# RJ45.net
KiCad netlist of a schematic drawn in Altium Designer
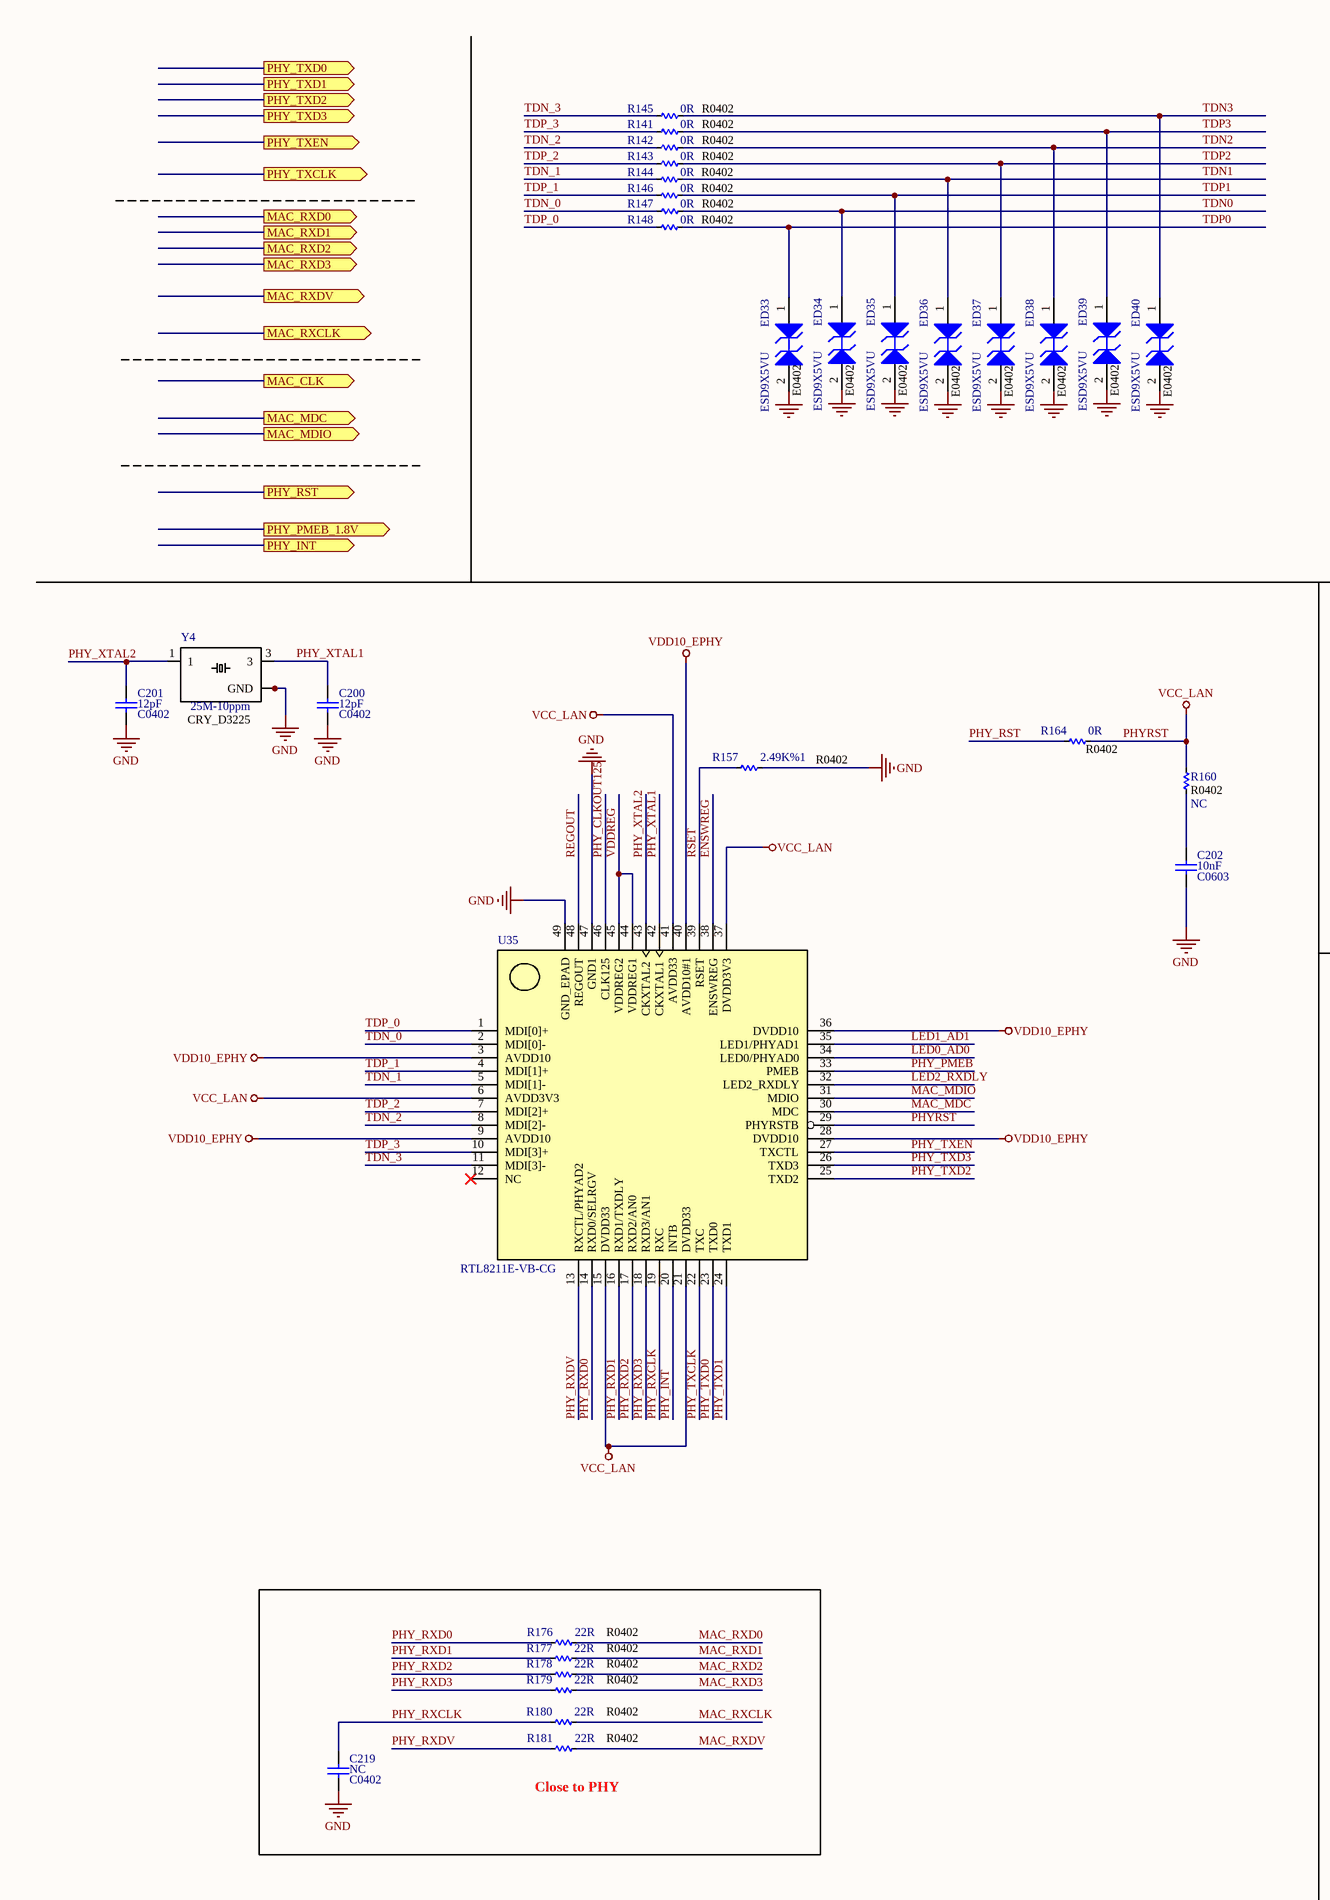
[diagram p0: RJ45.SchDoc, left]
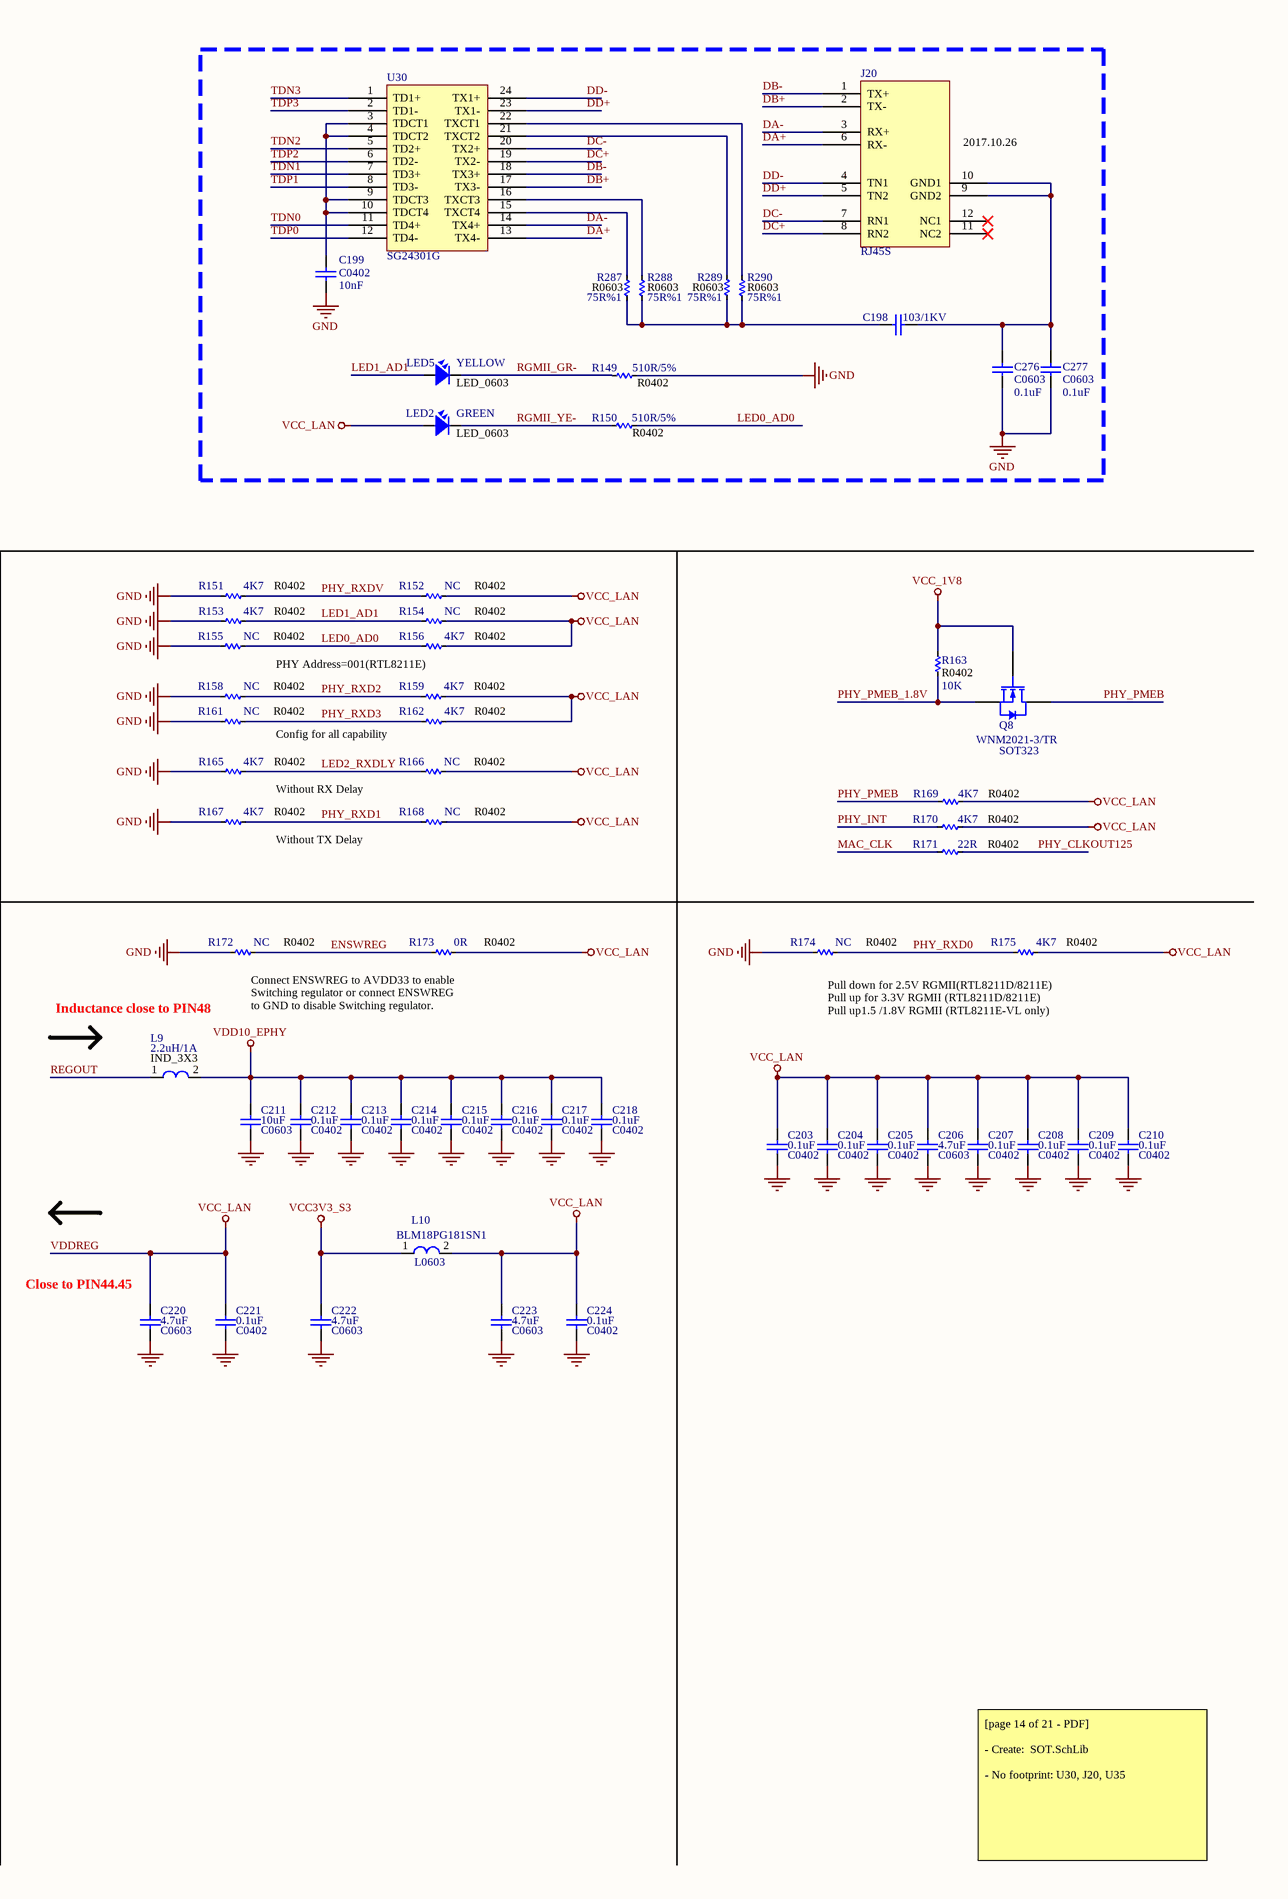
[diagram p1: RJ45.SchDoc, right]

(export (version "E")
  (design (tool "Eeschema 10.0.6"))
  (components
    (comp (ref "C198")
      (value "103/1KV")
      (footprint "C 1206")
      (description "Capacitor")
      (fields (field (name "Comment") "C1206"))
      (libsource (lib "Miscellaneous Devices") (part "Cap"))
    )
    (comp (ref "C199")
      (value "C0402")
      (footprint "C 0402")
      (description "Capacitor")
      (fields (field (name "ALTIUM_VALUE") "10nF"))
      (libsource (lib "Miscellaneous Devices") (part "Cap"))
    )
    (comp (ref "C200")
      (value "C0402")
      (footprint "C 0402")
      (description "Capacitor")
      (fields (field (name "ALTIUM_VALUE") "12pF"))
      (libsource (lib "Miscellaneous Devices") (part "Cap"))
    )
    (comp (ref "C201")
      (value "C0402")
      (footprint "C 0402")
      (description "Capacitor")
      (fields (field (name "ALTIUM_VALUE") "12pF"))
      (libsource (lib "Miscellaneous Devices") (part "Cap"))
    )
    (comp (ref "C202")
      (value "C0603")
      (footprint "C 0603")
      (description "Capacitor")
      (fields (field (name "ALTIUM_VALUE") "10nF"))
      (libsource (lib "Miscellaneous Devices") (part "Cap"))
    )
    (comp (ref "C203")
      (value "C0402")
      (footprint "C 0402")
      (description "Capacitor")
      (fields (field (name "ALTIUM_VALUE") "0.1uF"))
      (libsource (lib "Miscellaneous Devices") (part "Cap"))
    )
    (comp (ref "C204")
      (value "C0402")
      (footprint "C 0402")
      (description "Capacitor")
      (fields (field (name "ALTIUM_VALUE") "0.1uF"))
      (libsource (lib "Miscellaneous Devices") (part "Cap"))
    )
    (comp (ref "C205")
      (value "C0402")
      (footprint "C 0402")
      (description "Capacitor")
      (fields (field (name "ALTIUM_VALUE") "0.1uF"))
      (libsource (lib "Miscellaneous Devices") (part "Cap"))
    )
    (comp (ref "C206")
      (value "C0603")
      (footprint "C 0603")
      (description "Capacitor")
      (fields (field (name "ALTIUM_VALUE") "4.7uF"))
      (libsource (lib "Miscellaneous Devices") (part "Cap"))
    )
    (comp (ref "C207")
      (value "C0402")
      (footprint "C 0402")
      (description "Capacitor")
      (fields (field (name "ALTIUM_VALUE") "0.1uF"))
      (libsource (lib "Miscellaneous Devices") (part "Cap"))
    )
    (comp (ref "C208")
      (value "C0402")
      (footprint "C 0402")
      (description "Capacitor")
      (fields (field (name "ALTIUM_VALUE") "0.1uF"))
      (libsource (lib "Miscellaneous Devices") (part "Cap"))
    )
    (comp (ref "C209")
      (value "C0402")
      (footprint "C 0402")
      (description "Capacitor")
      (fields (field (name "ALTIUM_VALUE") "0.1uF"))
      (libsource (lib "Miscellaneous Devices") (part "Cap"))
    )
    (comp (ref "C210")
      (value "C0402")
      (footprint "C 0402")
      (description "Capacitor")
      (fields (field (name "ALTIUM_VALUE") "0.1uF"))
      (libsource (lib "Miscellaneous Devices") (part "Cap"))
    )
    (comp (ref "C211")
      (value "C0603")
      (footprint "C 0603")
      (description "Capacitor")
      (fields (field (name "ALTIUM_VALUE") "10uF"))
      (libsource (lib "Miscellaneous Devices") (part "Cap"))
    )
    (comp (ref "C212")
      (value "C0402")
      (footprint "C 0402")
      (description "Capacitor")
      (fields (field (name "ALTIUM_VALUE") "0.1uF"))
      (libsource (lib "Miscellaneous Devices") (part "Cap"))
    )
    (comp (ref "C213")
      (value "C0402")
      (footprint "C 0402")
      (description "Capacitor")
      (fields (field (name "ALTIUM_VALUE") "0.1uF"))
      (libsource (lib "Miscellaneous Devices") (part "Cap"))
    )
    (comp (ref "C214")
      (value "C0402")
      (footprint "C 0402")
      (description "Capacitor")
      (fields (field (name "ALTIUM_VALUE") "0.1uF"))
      (libsource (lib "Miscellaneous Devices") (part "Cap"))
    )
    (comp (ref "C215")
      (value "C0402")
      (footprint "C 0402")
      (description "Capacitor")
      (fields (field (name "ALTIUM_VALUE") "0.1uF"))
      (libsource (lib "Miscellaneous Devices") (part "Cap"))
    )
    (comp (ref "C216")
      (value "C0402")
      (footprint "C 0402")
      (description "Capacitor")
      (fields (field (name "ALTIUM_VALUE") "0.1uF"))
      (libsource (lib "Miscellaneous Devices") (part "Cap"))
    )
    (comp (ref "C217")
      (value "C0402")
      (footprint "C 0402")
      (description "Capacitor")
      (fields (field (name "ALTIUM_VALUE") "0.1uF"))
      (libsource (lib "Miscellaneous Devices") (part "Cap"))
    )
    (comp (ref "C218")
      (value "C0402")
      (footprint "C 0402")
      (description "Capacitor")
      (fields (field (name "ALTIUM_VALUE") "0.1uF"))
      (libsource (lib "Miscellaneous Devices") (part "Cap"))
    )
    (comp (ref "C219")
      (value "C0402")
      (footprint "C 0402")
      (description "Capacitor")
      (fields (field (name "ALTIUM_VALUE") "NC"))
      (libsource (lib "Miscellaneous Devices") (part "Cap"))
    )
    (comp (ref "C220")
      (value "C0603")
      (footprint "C 0603")
      (description "Capacitor")
      (fields (field (name "ALTIUM_VALUE") "4.7uF"))
      (libsource (lib "Miscellaneous Devices") (part "Cap"))
    )
    (comp (ref "C221")
      (value "C0402")
      (footprint "C 0402")
      (description "Capacitor")
      (fields (field (name "ALTIUM_VALUE") "0.1uF"))
      (libsource (lib "Miscellaneous Devices") (part "Cap"))
    )
    (comp (ref "C222")
      (value "C0603")
      (footprint "C 0603")
      (description "Capacitor")
      (fields (field (name "ALTIUM_VALUE") "4.7uF"))
      (libsource (lib "Miscellaneous Devices") (part "Cap"))
    )
    (comp (ref "C223")
      (value "C0603")
      (footprint "C 0603")
      (description "Capacitor")
      (fields (field (name "ALTIUM_VALUE") "4.7uF"))
      (libsource (lib "Miscellaneous Devices") (part "Cap"))
    )
    (comp (ref "C224")
      (value "C0402")
      (footprint "C 0402")
      (description "Capacitor")
      (fields (field (name "ALTIUM_VALUE") "0.1uF"))
      (libsource (lib "Miscellaneous Devices") (part "Cap"))
    )
    (comp (ref "C276")
      (value "C0603")
      (footprint "C 0603")
      (description "Capacitor")
      (fields (field (name "ALTIUM_VALUE") "0.1uF"))
      (libsource (lib "Miscellaneous Devices") (part "Cap"))
    )
    (comp (ref "C277")
      (value "C0603")
      (footprint "C 0603")
      (description "Capacitor")
      (fields (field (name "ALTIUM_VALUE") "0.1uF"))
      (libsource (lib "Miscellaneous Devices") (part "Cap"))
    )
    (comp (ref "ED33")
      (value "ESD9X5VU")
      (footprint "DFN1006-2L")
      (description "600 W Peak Power Zener Transient Voltage Suppressor, Bidirectional, 2-Pin SMB, Tape and Reel")
      (fields
        (field (name "MANUFACTURER") "On Semiconductor")
        (field (name "PARTNUMBER") "1SMB54CAT3")
        (field (name "SIZE") "E0402")
      )
      (libsource (lib "ON Semi Transient Voltage Suppressors (TVS)") (part "1SMB54CAT3"))
    )
    (comp (ref "ED34")
      (value "ESD9X5VU")
      (footprint "DFN1006-2L")
      (description "600 W Peak Power Zener Transient Voltage Suppressor, Bidirectional, 2-Pin SMB, Tape and Reel")
      (fields
        (field (name "MANUFACTURER") "On Semiconductor")
        (field (name "PARTNUMBER") "1SMB54CAT3")
        (field (name "SIZE") "E0402")
      )
      (libsource (lib "ON Semi Transient Voltage Suppressors (TVS)") (part "1SMB54CAT3"))
    )
    (comp (ref "ED35")
      (value "ESD9X5VU")
      (footprint "DFN1006-2L")
      (description "600 W Peak Power Zener Transient Voltage Suppressor, Bidirectional, 2-Pin SMB, Tape and Reel")
      (fields
        (field (name "MANUFACTURER") "On Semiconductor")
        (field (name "PARTNUMBER") "1SMB54CAT3")
        (field (name "SIZE") "E0402")
      )
      (libsource (lib "ON Semi Transient Voltage Suppressors (TVS)") (part "1SMB54CAT3"))
    )
    (comp (ref "ED36")
      (value "ESD9X5VU")
      (footprint "DFN1006-2L")
      (description "600 W Peak Power Zener Transient Voltage Suppressor, Bidirectional, 2-Pin SMB, Tape and Reel")
      (fields
        (field (name "MANUFACTURER") "On Semiconductor")
        (field (name "PARTNUMBER") "1SMB54CAT3")
        (field (name "SIZE") "E0402")
      )
      (libsource (lib "ON Semi Transient Voltage Suppressors (TVS)") (part "1SMB54CAT3"))
    )
    (comp (ref "ED37")
      (value "ESD9X5VU")
      (footprint "DFN1006-2L")
      (description "600 W Peak Power Zener Transient Voltage Suppressor, Bidirectional, 2-Pin SMB, Tape and Reel")
      (fields
        (field (name "MANUFACTURER") "On Semiconductor")
        (field (name "PARTNUMBER") "1SMB54CAT3")
        (field (name "SIZE") "E0402")
      )
      (libsource (lib "ON Semi Transient Voltage Suppressors (TVS)") (part "1SMB54CAT3"))
    )
    (comp (ref "ED38")
      (value "ESD9X5VU")
      (footprint "DFN1006-2L")
      (description "600 W Peak Power Zener Transient Voltage Suppressor, Bidirectional, 2-Pin SMB, Tape and Reel")
      (fields
        (field (name "MANUFACTURER") "On Semiconductor")
        (field (name "PARTNUMBER") "1SMB54CAT3")
        (field (name "SIZE") "E0402")
      )
      (libsource (lib "ON Semi Transient Voltage Suppressors (TVS)") (part "1SMB54CAT3"))
    )
    (comp (ref "ED39")
      (value "ESD9X5VU")
      (footprint "DFN1006-2L")
      (description "600 W Peak Power Zener Transient Voltage Suppressor, Bidirectional, 2-Pin SMB, Tape and Reel")
      (fields
        (field (name "MANUFACTURER") "On Semiconductor")
        (field (name "PARTNUMBER") "1SMB54CAT3")
        (field (name "SIZE") "E0402")
      )
      (libsource (lib "ON Semi Transient Voltage Suppressors (TVS)") (part "1SMB54CAT3"))
    )
    (comp (ref "ED40")
      (value "ESD9X5VU")
      (footprint "DFN1006-2L")
      (description "600 W Peak Power Zener Transient Voltage Suppressor, Bidirectional, 2-Pin SMB, Tape and Reel")
      (fields
        (field (name "MANUFACTURER") "On Semiconductor")
        (field (name "PARTNUMBER") "1SMB54CAT3")
        (field (name "SIZE") "E0402")
      )
      (libsource (lib "ON Semi Transient Voltage Suppressors (TVS)") (part "1SMB54CAT3"))
    )
    (comp (ref "J20") (value "RJ45S") (footprint "RJ45") (libsource (lib "SOT") (part "RJ45S")))
    (comp (ref "L9")
      (value "2.2uH/1A")
      (footprint "L-SMD-M-7.3x4.5")
      (fields
        (field (name "PARTNO") "78477010")
        (field (name "MANUFACTURER") "Wurth Elektronik")
        (field (name "ALTIUM_UNNAMED_1") "IND_3X3")
      )
      (libsource (lib "LIBRARY") (part "L-SMD-1"))
    )
    (comp (ref "L10")
      (value "L0603")
      (footprint "L-SMD-M-12x10")
      (fields
        (field (name "PARTNO") "78477010")
        (field (name "MANUFACTURER") "Wurth Elektronik")
        (field (name "ALTIUM_UNNAMED_1") "BLM18PG181SN1")
      )
      (libsource (lib "LIBRARY") (part "L-SMD-1"))
    )
    (comp (ref "LED2")
      (value "LED SMD")
      (footprint "SM-LED-0805-Green")
      (fields (field (name "PACKAGE") "LED_0603") (field (name "COLOR") "GREEN"))
      (libsource (lib "syhaunguyen") (part "LED-SMD-0805"))
    )
    (comp (ref "LED5")
      (value "LED SMD")
      (footprint "SM-LED-0805-Yellow")
      (fields (field (name "PACKAGE") "LED_0603") (field (name "COLOR") "YELLOW"))
      (libsource (lib "syhaunguyen") (part "LED-SMD-0805"))
    )
    (comp (ref "Q8")
      (value "WNM2021-3/TR")
      (footprint "SOT23")
      (description "20V N-Channel Enhancement Mode MOSFET")
      (fields (field (name "PACKAGEREFERENCE") "SOT323"))
      (libsource (lib "Zetex Discrete MOSFET") (part "ZXM61N02F"))
    )
    (comp (ref "R141")
      (value "R0402")
      (footprint "R 0402")
      (description "Resistor")
      (fields (field (name "MANUFACTURER") "Generic Components") (field (name "ALTIUM_VALUE") "0R"))
      (libsource (lib "LIBRARY") (part "Res-SMD"))
    )
    (comp (ref "R142")
      (value "R0402")
      (footprint "R 0402")
      (description "Resistor")
      (fields (field (name "MANUFACTURER") "Generic Components") (field (name "ALTIUM_VALUE") "0R"))
      (libsource (lib "LIBRARY") (part "Res-SMD"))
    )
    (comp (ref "R143")
      (value "R0402")
      (footprint "R 0402")
      (description "Resistor")
      (fields (field (name "MANUFACTURER") "Generic Components") (field (name "ALTIUM_VALUE") "0R"))
      (libsource (lib "LIBRARY") (part "Res-SMD"))
    )
    (comp (ref "R144")
      (value "R0402")
      (footprint "R 0402")
      (description "Resistor")
      (fields (field (name "MANUFACTURER") "Generic Components") (field (name "ALTIUM_VALUE") "0R"))
      (libsource (lib "LIBRARY") (part "Res-SMD"))
    )
    (comp (ref "R145")
      (value "R0402")
      (footprint "R 0402")
      (description "Resistor")
      (fields (field (name "MANUFACTURER") "Generic Components") (field (name "ALTIUM_VALUE") "0R"))
      (libsource (lib "LIBRARY") (part "Res-SMD"))
    )
    (comp (ref "R146")
      (value "R0402")
      (footprint "R 0402")
      (description "Resistor")
      (fields (field (name "MANUFACTURER") "Generic Components") (field (name "ALTIUM_VALUE") "0R"))
      (libsource (lib "LIBRARY") (part "Res-SMD"))
    )
    (comp (ref "R147")
      (value "R0402")
      (footprint "R 0402")
      (description "Resistor")
      (fields (field (name "MANUFACTURER") "Generic Components") (field (name "ALTIUM_VALUE") "0R"))
      (libsource (lib "LIBRARY") (part "Res-SMD"))
    )
    (comp (ref "R148")
      (value "R0402")
      (footprint "R 0402")
      (description "Resistor")
      (fields (field (name "MANUFACTURER") "Generic Components") (field (name "ALTIUM_VALUE") "0R"))
      (libsource (lib "LIBRARY") (part "Res-SMD"))
    )
    (comp (ref "R149")
      (value "R0402")
      (footprint "R 0402")
      (description "Resistor")
      (fields (field (name "MANUFACTURER") "Generic Components") (field (name "ALTIUM_VALUE") "510R/5%"))
      (libsource (lib "LIBRARY") (part "Res-SMD"))
    )
    (comp (ref "R150")
      (value "R0402")
      (footprint "R 0402")
      (description "Resistor")
      (fields (field (name "MANUFACTURER") "Generic Components") (field (name "ALTIUM_VALUE") "510R/5%"))
      (libsource (lib "LIBRARY") (part "Res-SMD"))
    )
    (comp (ref "R151")
      (value "R0402")
      (footprint "R 0402")
      (description "Resistor")
      (fields (field (name "MANUFACTURER") "Generic Components") (field (name "ALTIUM_VALUE") "4K7"))
      (libsource (lib "LIBRARY") (part "Res-SMD"))
    )
    (comp (ref "R152")
      (value "R0402")
      (footprint "R 0402")
      (description "Resistor")
      (fields (field (name "MANUFACTURER") "Generic Components") (field (name "ALTIUM_VALUE") "NC"))
      (libsource (lib "LIBRARY") (part "Res-SMD"))
    )
    (comp (ref "R153")
      (value "R0402")
      (footprint "R 0402")
      (description "Resistor")
      (fields (field (name "MANUFACTURER") "Generic Components") (field (name "ALTIUM_VALUE") "4K7"))
      (libsource (lib "LIBRARY") (part "Res-SMD"))
    )
    (comp (ref "R154")
      (value "R0402")
      (footprint "R 0402")
      (description "Resistor")
      (fields (field (name "MANUFACTURER") "Generic Components") (field (name "ALTIUM_VALUE") "NC"))
      (libsource (lib "LIBRARY") (part "Res-SMD"))
    )
    (comp (ref "R155")
      (value "R0402")
      (footprint "R 0402")
      (description "Resistor")
      (fields (field (name "MANUFACTURER") "Generic Components") (field (name "ALTIUM_VALUE") "NC"))
      (libsource (lib "LIBRARY") (part "Res-SMD"))
    )
    (comp (ref "R156")
      (value "R0402")
      (footprint "R 0402")
      (description "Resistor")
      (fields (field (name "MANUFACTURER") "Generic Components") (field (name "ALTIUM_VALUE") "4K7"))
      (libsource (lib "LIBRARY") (part "Res-SMD"))
    )
    (comp (ref "R157")
      (value "R0402")
      (footprint "R 0402")
      (description "Resistor")
      (fields (field (name "MANUFACTURER") "Generic Components") (field (name "ALTIUM_VALUE") "2.49K%1"))
      (libsource (lib "LIBRARY") (part "Res-SMD"))
    )
    (comp (ref "R158")
      (value "R0402")
      (footprint "R 0402")
      (description "Resistor")
      (fields (field (name "MANUFACTURER") "Generic Components") (field (name "ALTIUM_VALUE") "NC"))
      (libsource (lib "LIBRARY") (part "Res-SMD"))
    )
    (comp (ref "R159")
      (value "R0402")
      (footprint "R 0402")
      (description "Resistor")
      (fields (field (name "MANUFACTURER") "Generic Components") (field (name "ALTIUM_VALUE") "4K7"))
      (libsource (lib "LIBRARY") (part "Res-SMD"))
    )
    (comp (ref "R160")
      (value "R0402")
      (footprint "R 0402")
      (description "Resistor")
      (fields (field (name "MANUFACTURER") "Generic Components") (field (name "ALTIUM_VALUE") "NC"))
      (libsource (lib "LIBRARY") (part "Res-SMD"))
    )
    (comp (ref "R161")
      (value "R0402")
      (footprint "R 0402")
      (description "Resistor")
      (fields (field (name "MANUFACTURER") "Generic Components") (field (name "ALTIUM_VALUE") "NC"))
      (libsource (lib "LIBRARY") (part "Res-SMD"))
    )
    (comp (ref "R162")
      (value "R0402")
      (footprint "R 0402")
      (description "Resistor")
      (fields (field (name "MANUFACTURER") "Generic Components") (field (name "ALTIUM_VALUE") "4K7"))
      (libsource (lib "LIBRARY") (part "Res-SMD"))
    )
    (comp (ref "R163")
      (value "R0402")
      (footprint "R 0402")
      (description "Resistor")
      (fields (field (name "MANUFACTURER") "Generic Components") (field (name "ALTIUM_VALUE") "10K"))
      (libsource (lib "LIBRARY") (part "Res-SMD"))
    )
    (comp (ref "R164")
      (value "R0402")
      (footprint "R 0402")
      (description "Resistor")
      (fields (field (name "MANUFACTURER") "Generic Components") (field (name "ALTIUM_VALUE") "0R"))
      (libsource (lib "LIBRARY") (part "Res-SMD"))
    )
    (comp (ref "R165")
      (value "R0402")
      (footprint "R 0402")
      (description "Resistor")
      (fields (field (name "MANUFACTURER") "Generic Components") (field (name "ALTIUM_VALUE") "4K7"))
      (libsource (lib "LIBRARY") (part "Res-SMD"))
    )
    (comp (ref "R166")
      (value "R0402")
      (footprint "R 0402")
      (description "Resistor")
      (fields (field (name "MANUFACTURER") "Generic Components") (field (name "ALTIUM_VALUE") "NC"))
      (libsource (lib "LIBRARY") (part "Res-SMD"))
    )
    (comp (ref "R167")
      (value "R0402")
      (footprint "R 0402")
      (description "Resistor")
      (fields (field (name "MANUFACTURER") "Generic Components") (field (name "ALTIUM_VALUE") "4K7"))
      (libsource (lib "LIBRARY") (part "Res-SMD"))
    )
    (comp (ref "R168")
      (value "R0402")
      (footprint "R 0402")
      (description "Resistor")
      (fields (field (name "MANUFACTURER") "Generic Components") (field (name "ALTIUM_VALUE") "NC"))
      (libsource (lib "LIBRARY") (part "Res-SMD"))
    )
    (comp (ref "R169")
      (value "R0402")
      (footprint "R 0402")
      (description "Resistor")
      (fields (field (name "MANUFACTURER") "Generic Components") (field (name "ALTIUM_VALUE") "4K7"))
      (libsource (lib "LIBRARY") (part "Res-SMD"))
    )
    (comp (ref "R170")
      (value "R0402")
      (footprint "R 0402")
      (description "Resistor")
      (fields (field (name "MANUFACTURER") "Generic Components") (field (name "ALTIUM_VALUE") "4K7"))
      (libsource (lib "LIBRARY") (part "Res-SMD"))
    )
    (comp (ref "R171")
      (value "R0402")
      (footprint "R 0402")
      (description "Resistor")
      (fields (field (name "MANUFACTURER") "Generic Components") (field (name "ALTIUM_VALUE") "22R"))
      (libsource (lib "LIBRARY") (part "Res-SMD"))
    )
    (comp (ref "R172")
      (value "R0402")
      (footprint "R 0402")
      (description "Resistor")
      (fields (field (name "MANUFACTURER") "Generic Components") (field (name "ALTIUM_VALUE") "NC"))
      (libsource (lib "LIBRARY") (part "Res-SMD"))
    )
    (comp (ref "R173")
      (value "R0402")
      (footprint "R 0402")
      (description "Resistor")
      (fields (field (name "MANUFACTURER") "Generic Components") (field (name "ALTIUM_VALUE") "0R"))
      (libsource (lib "LIBRARY") (part "Res-SMD"))
    )
    (comp (ref "R174")
      (value "R0402")
      (footprint "R 0402")
      (description "Resistor")
      (fields (field (name "MANUFACTURER") "Generic Components") (field (name "ALTIUM_VALUE") "NC"))
      (libsource (lib "LIBRARY") (part "Res-SMD"))
    )
    (comp (ref "R175")
      (value "R0402")
      (footprint "R 0402")
      (description "Resistor")
      (fields (field (name "MANUFACTURER") "Generic Components") (field (name "ALTIUM_VALUE") "4K7"))
      (libsource (lib "LIBRARY") (part "Res-SMD"))
    )
    (comp (ref "R176")
      (value "R0402")
      (footprint "R 0402")
      (description "Resistor")
      (fields (field (name "MANUFACTURER") "Generic Components") (field (name "ALTIUM_VALUE") "22R"))
      (libsource (lib "LIBRARY") (part "Res-SMD"))
    )
    (comp (ref "R177")
      (value "R0402")
      (footprint "R 0402")
      (description "Resistor")
      (fields (field (name "MANUFACTURER") "Generic Components") (field (name "ALTIUM_VALUE") "22R"))
      (libsource (lib "LIBRARY") (part "Res-SMD"))
    )
    (comp (ref "R178")
      (value "R0402")
      (footprint "R 0402")
      (description "Resistor")
      (fields (field (name "MANUFACTURER") "Generic Components") (field (name "ALTIUM_VALUE") "22R"))
      (libsource (lib "LIBRARY") (part "Res-SMD"))
    )
    (comp (ref "R179")
      (value "R0402")
      (footprint "R 0402")
      (description "Resistor")
      (fields (field (name "MANUFACTURER") "Generic Components") (field (name "ALTIUM_VALUE") "22R"))
      (libsource (lib "LIBRARY") (part "Res-SMD"))
    )
    (comp (ref "R180")
      (value "R0402")
      (footprint "R 0402")
      (description "Resistor")
      (fields (field (name "MANUFACTURER") "Generic Components") (field (name "ALTIUM_VALUE") "22R"))
      (libsource (lib "LIBRARY") (part "Res-SMD"))
    )
    (comp (ref "R181")
      (value "R0402")
      (footprint "R 0402")
      (description "Resistor")
      (fields (field (name "MANUFACTURER") "Generic Components") (field (name "ALTIUM_VALUE") "22R"))
      (libsource (lib "LIBRARY") (part "Res-SMD"))
    )
    (comp (ref "R287")
      (value "R0603")
      (footprint "R 0603")
      (description "Resistor")
      (fields (field (name "MANUFACTURER") "Generic Components") (field (name "ALTIUM_VALUE") "75R%1"))
      (libsource (lib "LIBRARY") (part "Res-SMD"))
    )
    (comp (ref "R288")
      (value "R0603")
      (footprint "R 0603")
      (description "Resistor")
      (fields (field (name "MANUFACTURER") "Generic Components") (field (name "ALTIUM_VALUE") "75R%1"))
      (libsource (lib "LIBRARY") (part "Res-SMD"))
    )
    (comp (ref "R289")
      (value "R0603")
      (footprint "R 0603")
      (description "Resistor")
      (fields (field (name "MANUFACTURER") "Generic Components") (field (name "ALTIUM_VALUE") "75R%1"))
      (libsource (lib "LIBRARY") (part "Res-SMD"))
    )
    (comp (ref "R290")
      (value "R0603")
      (footprint "R 0603")
      (description "Resistor")
      (fields (field (name "MANUFACTURER") "Generic Components") (field (name "ALTIUM_VALUE") "75R%1"))
      (libsource (lib "LIBRARY") (part "Res-SMD"))
    )
    (comp (ref "U30") (value "SG24301G") (footprint "SG24301G") (libsource (lib "SOT") (part "SG24301G")))
    (comp (ref "U35")
      (value "RTL8211E-VB-CG")
      (footprint "QFN48")
      (libsource (lib "SOT") (part "RTL8211E-VB-CG"))
    )
    (comp (ref "Y4")
      (value "25M-10ppm")
      (footprint "Crystal 4-SMD 32x25")
      (description "Ultra Miniature Crystal, SMD Ceramic, 30.000MHZ, 10pF, 10ppm@25C, 10ppm -10+60C,")
      (fields
        (field (name "MF") "Abracon")
        (field (name "MP") "ABM8-30.000MHZ-10-1-U-T")
        (field (name "ALTIUM_UNNAMED_1") "CRY_D3225")
      )
      (libsource (lib "ABM8-30.000MHZ-10-1-U-T") (part "ABM8-30.000MHZ-10-1-U-T"))
    )
  )
  (nets
    (net (code "1") (name "/DA+") (class "Default")
      (node (ref "J20") (pin "6") (pinfunction "RX-_6") (pintype "passive"))
      (node (ref "U30") (pin "13") (pinfunction "TX4-_13") (pintype "passive"))
    )
    (net (code "2") (name "/DA-") (class "Default")
      (node (ref "J20") (pin "3") (pinfunction "RX+_3") (pintype "passive"))
      (node (ref "U30") (pin "14") (pinfunction "TX4+_14") (pintype "passive"))
    )
    (net (code "3") (name "/DB+") (class "Default")
      (node (ref "J20") (pin "2") (pinfunction "TX-_2") (pintype "passive"))
      (node (ref "U30") (pin "17") (pinfunction "TX3-_17") (pintype "passive"))
    )
    (net (code "4") (name "/DB-") (class "Default")
      (node (ref "J20") (pin "1") (pinfunction "TX+_1") (pintype "passive"))
      (node (ref "U30") (pin "18") (pinfunction "TX3+_18") (pintype "passive"))
    )
    (net (code "5") (name "/DC+") (class "Default")
      (node (ref "J20") (pin "8") (pinfunction "RN2_8") (pintype "passive"))
      (node (ref "U30") (pin "19") (pinfunction "TX2-_19") (pintype "passive"))
    )
    (net (code "6") (name "/DC-") (class "Default")
      (node (ref "J20") (pin "7") (pinfunction "RN1_7") (pintype "passive"))
      (node (ref "U30") (pin "20") (pinfunction "TX2+_20") (pintype "passive"))
    )
    (net (code "7") (name "/DD+") (class "Default")
      (node (ref "J20") (pin "5") (pinfunction "TN2_5") (pintype "passive"))
      (node (ref "U30") (pin "23") (pinfunction "TX1-_23") (pintype "passive"))
    )
    (net (code "8") (name "/DD-") (class "Default")
      (node (ref "J20") (pin "4") (pinfunction "TN1_4") (pintype "passive"))
      (node (ref "U30") (pin "24") (pinfunction "TX1+_24") (pintype "passive"))
    )
    (net (code "9") (name "/ENSWREG") (class "Default")
      (node (ref "R172") (pin "2") (pinfunction "2_2") (pintype "passive"))
      (node (ref "R173") (pin "1") (pinfunction "1_1") (pintype "passive"))
      (node (ref "U35") (pin "38") (pinfunction "ENSWREG_38") (pintype "passive"))
    )
    (net (code "10") (name "/LED0_AD0") (class "Default")
      (node (ref "R150") (pin "1") (pinfunction "1_1") (pintype "passive"))
      (node (ref "R155") (pin "2") (pinfunction "2_2") (pintype "passive"))
      (node (ref "R156") (pin "1") (pinfunction "1_1") (pintype "passive"))
      (node (ref "U35") (pin "34") (pinfunction "LED0/PHYAD0_34") (pintype "passive"))
    )
    (net (code "11") (name "/LED1_AD1") (class "Default")
      (node (ref "LED5") (pin "1") (pinfunction "1_1") (pintype "passive"))
      (node (ref "R153") (pin "2") (pinfunction "2_2") (pintype "passive"))
      (node (ref "R154") (pin "1") (pinfunction "1_1") (pintype "passive"))
      (node (ref "U35") (pin "35") (pinfunction "LED1/PHYAD1_35") (pintype "passive"))
    )
    (net (code "12") (name "/LED2_RXDLY") (class "Default")
      (node (ref "R165") (pin "2") (pinfunction "2_2") (pintype "passive"))
      (node (ref "R166") (pin "1") (pinfunction "1_1") (pintype "passive"))
      (node (ref "U35") (pin "32") (pinfunction "LED2_RXDLY_32") (pintype "passive"))
    )
    (net (code "13") (name "/MAC_CLK") (class "Default")
      (node (ref "R171") (pin "1") (pinfunction "1_1") (pintype "passive"))
    )
    (net (code "14") (name "/MAC_MDC") (class "Default")
      (node (ref "U35") (pin "30") (pinfunction "MDC_30") (pintype "passive"))
    )
    (net (code "15") (name "/MAC_MDIO") (class "Default")
      (node (ref "U35") (pin "31") (pinfunction "MDIO_31") (pintype "passive"))
    )
    (net (code "16") (name "/MAC_RXCLK") (class "Default")
      (node (ref "R180") (pin "2") (pinfunction "2_2") (pintype "passive"))
    )
    (net (code "17") (name "/MAC_RXD0") (class "Default")
      (node (ref "R176") (pin "2") (pinfunction "2_2") (pintype "passive"))
    )
    (net (code "18") (name "/MAC_RXD1") (class "Default")
      (node (ref "R177") (pin "2") (pinfunction "2_2") (pintype "passive"))
    )
    (net (code "19") (name "/MAC_RXD2") (class "Default")
      (node (ref "R178") (pin "2") (pinfunction "2_2") (pintype "passive"))
    )
    (net (code "20") (name "/MAC_RXD3") (class "Default")
      (node (ref "R179") (pin "2") (pinfunction "2_2") (pintype "passive"))
    )
    (net (code "21") (name "/MAC_RXDV") (class "Default")
      (node (ref "R181") (pin "2") (pinfunction "2_2") (pintype "passive"))
    )
    (net (code "22") (name "/PHY_CLKOUT125") (class "Default")
      (node (ref "R171") (pin "2") (pinfunction "2_2") (pintype "passive"))
      (node (ref "U35") (pin "46") (pinfunction "CLK125_46") (pintype "passive"))
    )
    (net (code "23") (name "/PHY_INT") (class "Default")
      (node (ref "R170") (pin "1") (pinfunction "1_1") (pintype "passive"))
      (node (ref "U35") (pin "20") (pinfunction "INTB_20") (pintype "passive"))
    )
    (net (code "24") (name "/PHY_PMEB") (class "Default")
      (node (ref "Q8") (pin "1") (pinfunction "D_1") (pintype "passive"))
      (node (ref "R169") (pin "1") (pinfunction "1_1") (pintype "passive"))
      (node (ref "U35") (pin "33") (pinfunction "PMEB_33") (pintype "passive"))
    )
    (net (code "25") (name "/PHY_PMEB_1.8V") (class "Default")
      (node (ref "Q8") (pin "2") (pinfunction "S_2") (pintype "passive"))
      (node (ref "R163") (pin "2") (pinfunction "2_2") (pintype "passive"))
    )
    (net (code "26") (name "/PHY_RST") (class "Default")
      (node (ref "R164") (pin "1") (pinfunction "1_1") (pintype "passive"))
    )
    (net (code "27") (name "/PHY_RXCLK") (class "Default")
      (node (ref "C219") (pin "1") (pinfunction "1_1") (pintype "passive"))
      (node (ref "R180") (pin "1") (pinfunction "1_1") (pintype "passive"))
      (node (ref "U35") (pin "19") (pinfunction "RXC_19") (pintype "passive"))
    )
    (net (code "28") (name "/PHY_RXD0") (class "Default")
      (node (ref "R174") (pin "2") (pinfunction "2_2") (pintype "passive"))
      (node (ref "R175") (pin "1") (pinfunction "1_1") (pintype "passive"))
      (node (ref "R176") (pin "1") (pinfunction "1_1") (pintype "passive"))
      (node (ref "U35") (pin "14") (pinfunction "RXD0/SELRGV_14") (pintype "passive"))
    )
    (net (code "29") (name "/PHY_RXD1") (class "Default")
      (node (ref "R167") (pin "2") (pinfunction "2_2") (pintype "passive"))
      (node (ref "R168") (pin "1") (pinfunction "1_1") (pintype "passive"))
      (node (ref "R177") (pin "1") (pinfunction "1_1") (pintype "passive"))
      (node (ref "U35") (pin "16") (pinfunction "RXD1/TXDLY_16") (pintype "passive"))
    )
    (net (code "30") (name "/PHY_RXD2") (class "Default")
      (node (ref "R158") (pin "2") (pinfunction "2_2") (pintype "passive"))
      (node (ref "R159") (pin "1") (pinfunction "1_1") (pintype "passive"))
      (node (ref "R178") (pin "1") (pinfunction "1_1") (pintype "passive"))
      (node (ref "U35") (pin "17") (pinfunction "RXD2/AN0_17") (pintype "passive"))
    )
    (net (code "31") (name "/PHY_RXD3") (class "Default")
      (node (ref "R161") (pin "2") (pinfunction "2_2") (pintype "passive"))
      (node (ref "R162") (pin "1") (pinfunction "1_1") (pintype "passive"))
      (node (ref "R179") (pin "1") (pinfunction "1_1") (pintype "passive"))
      (node (ref "U35") (pin "18") (pinfunction "RXD3/AN1_18") (pintype "passive"))
    )
    (net (code "32") (name "/PHY_RXDV") (class "Default")
      (node (ref "R151") (pin "2") (pinfunction "2_2") (pintype "passive"))
      (node (ref "R152") (pin "1") (pinfunction "1_1") (pintype "passive"))
      (node (ref "R181") (pin "1") (pinfunction "1_1") (pintype "passive"))
      (node (ref "U35") (pin "13") (pinfunction "RXCTL/PHYAD2_13") (pintype "passive"))
    )
    (net (code "33") (name "/PHY_TXCLK") (class "Default")
      (node (ref "U35") (pin "22") (pinfunction "TXC_22") (pintype "passive"))
    )
    (net (code "34") (name "/PHY_TXD0") (class "Default")
      (node (ref "U35") (pin "23") (pinfunction "TXD0_23") (pintype "passive"))
    )
    (net (code "35") (name "/PHY_TXD1") (class "Default")
      (node (ref "U35") (pin "24") (pinfunction "TXD1_24") (pintype "passive"))
    )
    (net (code "36") (name "/PHY_TXD2") (class "Default")
      (node (ref "U35") (pin "25") (pinfunction "TXD2_25") (pintype "passive"))
    )
    (net (code "37") (name "/PHY_TXD3") (class "Default")
      (node (ref "U35") (pin "26") (pinfunction "TXD3_26") (pintype "passive"))
    )
    (net (code "38") (name "/PHY_TXEN") (class "Default")
      (node (ref "U35") (pin "27") (pinfunction "TXCTL_27") (pintype "passive"))
    )
    (net (code "39") (name "/PHY_XTAL1") (class "Default")
      (node (ref "C200") (pin "1") (pinfunction "1_1") (pintype "passive"))
      (node (ref "U35") (pin "42") (pinfunction "CKXTAL1_42") (pintype "passive"))
      (node (ref "Y4") (pin "3") (pinfunction "3_3") (pintype "passive"))
    )
    (net (code "40") (name "/PHY_XTAL2") (class "Default")
      (node (ref "C201") (pin "1") (pinfunction "1_1") (pintype "passive"))
      (node (ref "U35") (pin "43") (pinfunction "CKXTAL2_43") (pintype "passive"))
      (node (ref "Y4") (pin "1") (pinfunction "1_1") (pintype "passive"))
    )
    (net (code "41") (name "/REGOUT") (class "Default")
      (node (ref "L9") (pin "1") (pinfunction "1_1") (pintype "passive"))
      (node (ref "U35") (pin "48") (pinfunction "REGOUT_48") (pintype "passive"))
    )
    (net (code "42") (name "/RGMII_GR-") (class "Default")
      (node (ref "LED5") (pin "2") (pinfunction "2_2") (pintype "passive"))
      (node (ref "R149") (pin "2") (pinfunction "2_2") (pintype "passive"))
    )
    (net (code "43") (name "/RGMII_YE-") (class "Default")
      (node (ref "LED2") (pin "2") (pinfunction "2_2") (pintype "passive"))
      (node (ref "R150") (pin "2") (pinfunction "2_2") (pintype "passive"))
    )
    (net (code "44") (name "/RSET") (class "Default")
      (node (ref "R157") (pin "1") (pinfunction "1_1") (pintype "passive"))
      (node (ref "U35") (pin "39") (pinfunction "RSET_39") (pintype "passive"))
    )
    (net (code "45") (name "/TDN0") (class "Default")
      (node (ref "ED34") (pin "1") (pinfunction "A1_1") (pintype "passive"))
      (node (ref "R147") (pin "2") (pinfunction "2_2") (pintype "passive"))
      (node (ref "U30") (pin "11") (pinfunction "TD4+_11") (pintype "passive"))
    )
    (net (code "46") (name "/TDN1") (class "Default")
      (node (ref "ED36") (pin "1") (pinfunction "A1_1") (pintype "passive"))
      (node (ref "R144") (pin "2") (pinfunction "2_2") (pintype "passive"))
      (node (ref "U30") (pin "7") (pinfunction "TD3+_7") (pintype "passive"))
    )
    (net (code "47") (name "/TDN2") (class "Default")
      (node (ref "ED38") (pin "1") (pinfunction "A1_1") (pintype "passive"))
      (node (ref "R142") (pin "2") (pinfunction "2_2") (pintype "passive"))
      (node (ref "U30") (pin "5") (pinfunction "TD2+_5") (pintype "passive"))
    )
    (net (code "48") (name "/TDN3") (class "Default")
      (node (ref "ED40") (pin "1") (pinfunction "A1_1") (pintype "passive"))
      (node (ref "R145") (pin "2") (pinfunction "2_2") (pintype "passive"))
      (node (ref "U30") (pin "1") (pinfunction "TD1+_1") (pintype "passive"))
    )
    (net (code "49") (name "/TDN_0") (class "Default")
      (node (ref "R147") (pin "1") (pinfunction "1_1") (pintype "passive"))
      (node (ref "U35") (pin "2") (pinfunction "MDI[0]-_2") (pintype "passive"))
    )
    (net (code "50") (name "/TDN_1") (class "Default")
      (node (ref "R144") (pin "1") (pinfunction "1_1") (pintype "passive"))
      (node (ref "U35") (pin "5") (pinfunction "MDI[1]-_5") (pintype "passive"))
    )
    (net (code "51") (name "/TDN_2") (class "Default")
      (node (ref "R142") (pin "1") (pinfunction "1_1") (pintype "passive"))
      (node (ref "U35") (pin "8") (pinfunction "MDI[2]-_8") (pintype "passive"))
    )
    (net (code "52") (name "/TDN_3") (class "Default")
      (node (ref "R145") (pin "1") (pinfunction "1_1") (pintype "passive"))
      (node (ref "U35") (pin "11") (pinfunction "MDI[3]-_11") (pintype "passive"))
    )
    (net (code "53") (name "/TDP0") (class "Default")
      (node (ref "ED33") (pin "1") (pinfunction "A1_1") (pintype "passive"))
      (node (ref "R148") (pin "2") (pinfunction "2_2") (pintype "passive"))
      (node (ref "U30") (pin "12") (pinfunction "TD4-_12") (pintype "passive"))
    )
    (net (code "54") (name "/TDP1") (class "Default")
      (node (ref "ED35") (pin "1") (pinfunction "A1_1") (pintype "passive"))
      (node (ref "R146") (pin "2") (pinfunction "2_2") (pintype "passive"))
      (node (ref "U30") (pin "8") (pinfunction "TD3-_8") (pintype "passive"))
    )
    (net (code "55") (name "/TDP2") (class "Default")
      (node (ref "ED37") (pin "1") (pinfunction "A1_1") (pintype "passive"))
      (node (ref "R143") (pin "2") (pinfunction "2_2") (pintype "passive"))
      (node (ref "U30") (pin "6") (pinfunction "TD2-_6") (pintype "passive"))
    )
    (net (code "56") (name "/TDP3") (class "Default")
      (node (ref "ED39") (pin "1") (pinfunction "A1_1") (pintype "passive"))
      (node (ref "R141") (pin "2") (pinfunction "2_2") (pintype "passive"))
      (node (ref "U30") (pin "2") (pinfunction "TD1-_2") (pintype "passive"))
    )
    (net (code "57") (name "/TDP_0") (class "Default")
      (node (ref "R148") (pin "1") (pinfunction "1_1") (pintype "passive"))
      (node (ref "U35") (pin "1") (pinfunction "MDI[0]+_1") (pintype "passive"))
    )
    (net (code "58") (name "/TDP_1") (class "Default")
      (node (ref "R146") (pin "1") (pinfunction "1_1") (pintype "passive"))
      (node (ref "U35") (pin "4") (pinfunction "MDI[1]+_4") (pintype "passive"))
    )
    (net (code "59") (name "/TDP_2") (class "Default")
      (node (ref "R143") (pin "1") (pinfunction "1_1") (pintype "passive"))
      (node (ref "U35") (pin "7") (pinfunction "MDI[2]+_7") (pintype "passive"))
    )
    (net (code "60") (name "/TDP_3") (class "Default")
      (node (ref "R141") (pin "1") (pinfunction "1_1") (pintype "passive"))
      (node (ref "U35") (pin "10") (pinfunction "MDI[3]+_10") (pintype "passive"))
    )
    (net (code "61") (name "GND") (class "Default")
      (node (ref "C199") (pin "1") (pinfunction "1_1") (pintype "passive"))
      (node (ref "C200") (pin "2") (pinfunction "2_2") (pintype "passive"))
      (node (ref "C201") (pin "2") (pinfunction "2_2") (pintype "passive"))
      (node (ref "C202") (pin "2") (pinfunction "2_2") (pintype "passive"))
      (node (ref "C203") (pin "2") (pinfunction "2_2") (pintype "passive"))
      (node (ref "C204") (pin "2") (pinfunction "2_2") (pintype "passive"))
      (node (ref "C205") (pin "2") (pinfunction "2_2") (pintype "passive"))
      (node (ref "C206") (pin "2") (pinfunction "2_2") (pintype "passive"))
      (node (ref "C207") (pin "2") (pinfunction "2_2") (pintype "passive"))
      (node (ref "C208") (pin "2") (pinfunction "2_2") (pintype "passive"))
      (node (ref "C209") (pin "2") (pinfunction "2_2") (pintype "passive"))
      (node (ref "C210") (pin "2") (pinfunction "2_2") (pintype "passive"))
      (node (ref "C211") (pin "2") (pinfunction "2_2") (pintype "passive"))
      (node (ref "C212") (pin "2") (pinfunction "2_2") (pintype "passive"))
      (node (ref "C213") (pin "2") (pinfunction "2_2") (pintype "passive"))
      (node (ref "C214") (pin "2") (pinfunction "2_2") (pintype "passive"))
      (node (ref "C215") (pin "2") (pinfunction "2_2") (pintype "passive"))
      (node (ref "C216") (pin "2") (pinfunction "2_2") (pintype "passive"))
      (node (ref "C217") (pin "2") (pinfunction "2_2") (pintype "passive"))
      (node (ref "C218") (pin "2") (pinfunction "2_2") (pintype "passive"))
      (node (ref "C219") (pin "2") (pinfunction "2_2") (pintype "passive"))
      (node (ref "C220") (pin "2") (pinfunction "2_2") (pintype "passive"))
      (node (ref "C221") (pin "2") (pinfunction "2_2") (pintype "passive"))
      (node (ref "C222") (pin "2") (pinfunction "2_2") (pintype "passive"))
      (node (ref "C223") (pin "2") (pinfunction "2_2") (pintype "passive"))
      (node (ref "C224") (pin "2") (pinfunction "2_2") (pintype "passive"))
      (node (ref "C276") (pin "2") (pinfunction "2_2") (pintype "passive"))
      (node (ref "C277") (pin "2") (pinfunction "2_2") (pintype "passive"))
      (node (ref "ED33") (pin "2") (pinfunction "A2_2") (pintype "passive"))
      (node (ref "ED34") (pin "2") (pinfunction "A2_2") (pintype "passive"))
      (node (ref "ED35") (pin "2") (pinfunction "A2_2") (pintype "passive"))
      (node (ref "ED36") (pin "2") (pinfunction "A2_2") (pintype "passive"))
      (node (ref "ED37") (pin "2") (pinfunction "A2_2") (pintype "passive"))
      (node (ref "ED38") (pin "2") (pinfunction "A2_2") (pintype "passive"))
      (node (ref "ED39") (pin "2") (pinfunction "A2_2") (pintype "passive"))
      (node (ref "ED40") (pin "2") (pinfunction "A2_2") (pintype "passive"))
      (node (ref "R149") (pin "1") (pinfunction "1_1") (pintype "passive"))
      (node (ref "R151") (pin "1") (pinfunction "1_1") (pintype "passive"))
      (node (ref "R153") (pin "1") (pinfunction "1_1") (pintype "passive"))
      (node (ref "R155") (pin "1") (pinfunction "1_1") (pintype "passive"))
      (node (ref "R157") (pin "2") (pinfunction "2_2") (pintype "passive"))
      (node (ref "R158") (pin "1") (pinfunction "1_1") (pintype "passive"))
      (node (ref "R161") (pin "1") (pinfunction "1_1") (pintype "passive"))
      (node (ref "R165") (pin "1") (pinfunction "1_1") (pintype "passive"))
      (node (ref "R167") (pin "1") (pinfunction "1_1") (pintype "passive"))
      (node (ref "R172") (pin "1") (pinfunction "1_1") (pintype "passive"))
      (node (ref "R174") (pin "1") (pinfunction "1_1") (pintype "passive"))
      (node (ref "U35") (pin "47") (pinfunction "GND1_47") (pintype "passive"))
      (node (ref "U35") (pin "49") (pinfunction "GND_EPAD_49") (pintype "passive"))
      (node (ref "Y4") (pin "2") (pinfunction "GND_2") (pintype "power_in"))
      (node (ref "Y4") (pin "4") (pinfunction "GND_4") (pintype "power_in"))
    )
    (net (code "62") (name "Net-(C198-Pad2)") (class "Default")
      (node (ref "C198") (pin "2") (pinfunction "2_2") (pintype "passive"))
      (node (ref "R287") (pin "1") (pinfunction "1_1") (pintype "passive"))
      (node (ref "R288") (pin "1") (pinfunction "1_1") (pintype "passive"))
      (node (ref "R289") (pin "1") (pinfunction "1_1") (pintype "passive"))
      (node (ref "R290") (pin "1") (pinfunction "1_1") (pintype "passive"))
    )
    (net (code "63") (name "Net-(C202-Pad1)") (class "Default")
      (node (ref "C202") (pin "1") (pinfunction "1_1") (pintype "passive"))
      (node (ref "R160") (pin "1") (pinfunction "1_1") (pintype "passive"))
    )
    (net (code "64") (name "Net-(J20-GND1)") (class "Default")
      (node (ref "C198") (pin "1") (pinfunction "1_1") (pintype "passive"))
      (node (ref "C276") (pin "1") (pinfunction "1_1") (pintype "passive"))
      (node (ref "C277") (pin "1") (pinfunction "1_1") (pintype "passive"))
      (node (ref "J20") (pin "10") (pinfunction "GND1_10") (pintype "passive"))
      (node (ref "J20") (pin "9") (pinfunction "GND2_9") (pintype "passive"))
    )
    (net (code "65") (name "Net-(U30-TDCT1)") (class "Default")
      (node (ref "C199") (pin "2") (pinfunction "2_2") (pintype "passive"))
      (node (ref "U30") (pin "10") (pinfunction "TDCT4_10") (pintype "passive"))
      (node (ref "U30") (pin "3") (pinfunction "TDCT1_3") (pintype "passive"))
      (node (ref "U30") (pin "4") (pinfunction "TDCT2_4") (pintype "passive"))
      (node (ref "U30") (pin "9") (pinfunction "TDCT3_9") (pintype "passive"))
    )
    (net (code "66") (name "Net-(U30-TXCT1)") (class "Default")
      (node (ref "R290") (pin "2") (pinfunction "2_2") (pintype "passive"))
      (node (ref "U30") (pin "22") (pinfunction "TXCT1_22") (pintype "passive"))
    )
    (net (code "67") (name "Net-(U30-TXCT2)") (class "Default")
      (node (ref "R289") (pin "2") (pinfunction "2_2") (pintype "passive"))
      (node (ref "U30") (pin "21") (pinfunction "TXCT2_21") (pintype "passive"))
    )
    (net (code "68") (name "Net-(U30-TXCT3)") (class "Default")
      (node (ref "R288") (pin "2") (pinfunction "2_2") (pintype "passive"))
      (node (ref "U30") (pin "16") (pinfunction "TXCT3_16") (pintype "passive"))
    )
    (net (code "69") (name "Net-(U30-TXCT4)") (class "Default")
      (node (ref "R287") (pin "2") (pinfunction "2_2") (pintype "passive"))
      (node (ref "U30") (pin "15") (pinfunction "TXCT4_15") (pintype "passive"))
    )
    (net (code "70") (name "VCC3V3_S3") (class "Default")
      (node (ref "C222") (pin "1") (pinfunction "1_1") (pintype "passive"))
      (node (ref "L10") (pin "1") (pinfunction "1_1") (pintype "passive"))
    )
    (net (code "71") (name "VCC_1V8") (class "Default")
      (node (ref "Q8") (pin "3") (pinfunction "G_3") (pintype "passive"))
      (node (ref "R163") (pin "1") (pinfunction "1_1") (pintype "passive"))
    )
    (net (code "72") (name "VCC_LAN") (class "Default")
      (node (ref "C203") (pin "1") (pinfunction "1_1") (pintype "passive"))
      (node (ref "C204") (pin "1") (pinfunction "1_1") (pintype "passive"))
      (node (ref "C205") (pin "1") (pinfunction "1_1") (pintype "passive"))
      (node (ref "C206") (pin "1") (pinfunction "1_1") (pintype "passive"))
      (node (ref "C207") (pin "1") (pinfunction "1_1") (pintype "passive"))
      (node (ref "C208") (pin "1") (pinfunction "1_1") (pintype "passive"))
      (node (ref "C209") (pin "1") (pinfunction "1_1") (pintype "passive"))
      (node (ref "C210") (pin "1") (pinfunction "1_1") (pintype "passive"))
      (node (ref "C220") (pin "1") (pinfunction "1_1") (pintype "passive"))
      (node (ref "C221") (pin "1") (pinfunction "1_1") (pintype "passive"))
      (node (ref "C223") (pin "1") (pinfunction "1_1") (pintype "passive"))
      (node (ref "C224") (pin "1") (pinfunction "1_1") (pintype "passive"))
      (node (ref "L10") (pin "2") (pinfunction "2_2") (pintype "passive"))
      (node (ref "LED2") (pin "1") (pinfunction "1_1") (pintype "passive"))
      (node (ref "R152") (pin "2") (pinfunction "2_2") (pintype "passive"))
      (node (ref "R154") (pin "2") (pinfunction "2_2") (pintype "passive"))
      (node (ref "R156") (pin "2") (pinfunction "2_2") (pintype "passive"))
      (node (ref "R159") (pin "2") (pinfunction "2_2") (pintype "passive"))
      (node (ref "R160") (pin "2") (pinfunction "2_2") (pintype "passive"))
      (node (ref "R162") (pin "2") (pinfunction "2_2") (pintype "passive"))
      (node (ref "R164") (pin "2") (pinfunction "2_2") (pintype "passive"))
      (node (ref "R166") (pin "2") (pinfunction "2_2") (pintype "passive"))
      (node (ref "R168") (pin "2") (pinfunction "2_2") (pintype "passive"))
      (node (ref "R169") (pin "2") (pinfunction "2_2") (pintype "passive"))
      (node (ref "R170") (pin "2") (pinfunction "2_2") (pintype "passive"))
      (node (ref "R173") (pin "2") (pinfunction "2_2") (pintype "passive"))
      (node (ref "R175") (pin "2") (pinfunction "2_2") (pintype "passive"))
      (node (ref "U35") (pin "15") (pinfunction "DVDD33_15") (pintype "passive"))
      (node (ref "U35") (pin "21") (pinfunction "DVDD33_21") (pintype "passive"))
      (node (ref "U35") (pin "29") (pinfunction "PHYRSTB_29") (pintype "passive"))
      (node (ref "U35") (pin "37") (pinfunction "DVDD3V3_37") (pintype "passive"))
      (node (ref "U35") (pin "41") (pinfunction "AVDD33_41") (pintype "passive"))
      (node (ref "U35") (pin "44") (pinfunction "VDDREG1_44") (pintype "passive"))
      (node (ref "U35") (pin "45") (pinfunction "VDDREG2_45") (pintype "passive"))
      (node (ref "U35") (pin "6") (pinfunction "AVDD3V3_6") (pintype "passive"))
    )
    (net (code "73") (name "VDD10_EPHY") (class "Default")
      (node (ref "C211") (pin "1") (pinfunction "1_1") (pintype "passive"))
      (node (ref "C212") (pin "1") (pinfunction "1_1") (pintype "passive"))
      (node (ref "C213") (pin "1") (pinfunction "1_1") (pintype "passive"))
      (node (ref "C214") (pin "1") (pinfunction "1_1") (pintype "passive"))
      (node (ref "C215") (pin "1") (pinfunction "1_1") (pintype "passive"))
      (node (ref "C216") (pin "1") (pinfunction "1_1") (pintype "passive"))
      (node (ref "C217") (pin "1") (pinfunction "1_1") (pintype "passive"))
      (node (ref "C218") (pin "1") (pinfunction "1_1") (pintype "passive"))
      (node (ref "L9") (pin "2") (pinfunction "2_2") (pintype "passive"))
      (node (ref "U35") (pin "28") (pinfunction "DVDD10_28") (pintype "passive"))
      (node (ref "U35") (pin "3") (pinfunction "AVDD10_3") (pintype "passive"))
      (node (ref "U35") (pin "36") (pinfunction "DVDD10_36") (pintype "passive"))
      (node (ref "U35") (pin "40") (pinfunction "AVDD10#1_40") (pintype "passive"))
      (node (ref "U35") (pin "9") (pinfunction "AVDD10_9") (pintype "passive"))
    )
    (net (code "74") (name "unconnected-(J20-NC1-Pad12)") (class "Default")
      (node (ref "J20") (pin "12") (pinfunction "NC1_12") (pintype "passive+no_connect"))
    )
    (net (code "75") (name "unconnected-(J20-NC2-Pad11)") (class "Default")
      (node (ref "J20") (pin "11") (pinfunction "NC2_11") (pintype "passive+no_connect"))
    )
    (net (code "76") (name "unconnected-(U35-NC-Pad12)") (class "Default")
      (node (ref "U35") (pin "12") (pinfunction "NC_12") (pintype "passive+no_connect"))
    )
  )
)
